# opticalDecoder.net
KiCad netlist of a schematic drawn in Altium Designer
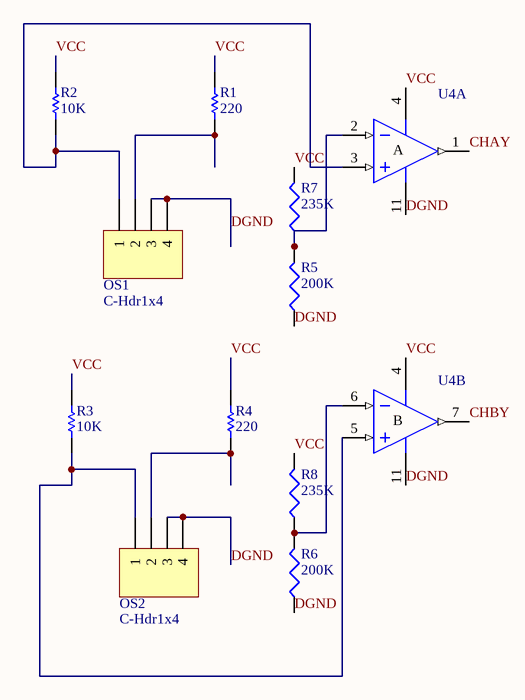
[diagram p0: opticalDecoder.SchDoc]

(export (version "E")
  (design (tool "Eeschema 10.0.6"))
  (components
    (comp (ref "OS1")
      (value "C-Hdr1x4")
      (footprint "HDR1X4_LGE1.0")
      (description "Header, 4-Pin")
      (fields (field (name "PUBLISHER") "Altium Limited"))
      (libsource (lib "PartsDatabaseV13p1") (part "C-Hdr1x4"))
    )
    (comp (ref "OS2")
      (value "C-Hdr1x4")
      (footprint "HDR1X4_LGE1.0")
      (description "Header, 4-Pin")
      (fields (field (name "PUBLISHER") "Altium Limited"))
      (libsource (lib "PartsDatabaseV13p1") (part "C-Hdr1x4"))
    )
    (comp (ref "R1")
      (value "220")
      (footprint "Res10mm_LGE1.0")
      (description "Resistor")
      (fields (field (name "PUBLISHER") "Altium Limited"))
      (libsource (lib "Miscellaneous Devices") (part "Res1"))
    )
    (comp (ref "R2")
      (value "10K")
      (footprint "Res10mm_LGE1.0")
      (description "Resistor")
      (fields (field (name "PUBLISHER") "Altium Limited"))
      (libsource (lib "Miscellaneous Devices") (part "Res1"))
    )
    (comp (ref "R3")
      (value "10K")
      (footprint "Res10mm_LGE1.0")
      (description "Resistor")
      (fields (field (name "PUBLISHER") "Altium Limited"))
      (libsource (lib "Miscellaneous Devices") (part "Res1"))
    )
    (comp (ref "R4")
      (value "220")
      (footprint "Res10mm_LGE1.0")
      (description "Resistor")
      (fields (field (name "PUBLISHER") "Altium Limited"))
      (libsource (lib "Miscellaneous Devices") (part "Res1"))
    )
    (comp (ref "R5")
      (value "200K")
      (footprint "Res10mm_LGE1.0")
      (description "resistor (specify value)")
      (fields (field (name "PUBLISHER") "Altium Limited"))
      (libsource (lib "PartsDatabaseV13p1") (part "G-Res"))
    )
    (comp (ref "R6")
      (value "200K")
      (footprint "Res10mm_LGE1.0")
      (description "resistor (specify value)")
      (fields (field (name "PUBLISHER") "Altium Limited"))
      (libsource (lib "PartsDatabaseV13p1") (part "G-Res"))
    )
    (comp (ref "R7")
      (value "235K")
      (footprint "Res10mm_LGE1.0")
      (description "resistor (specify value)")
      (fields (field (name "PUBLISHER") "Altium Limited"))
      (libsource (lib "PartsDatabaseV13p1") (part "G-Res"))
    )
    (comp (ref "R8")
      (value "235K")
      (footprint "Res10mm_LGE1.0")
      (description "resistor (specify value)")
      (fields (field (name "PUBLISHER") "Altium Limited"))
      (libsource (lib "PartsDatabaseV13p1") (part "G-Res"))
    )
    (comp (ref "U4")
      (value "O-OpAmp074")
      (footprint "DIP14_LGE1.0")
      (description "op amp (TL074)")
      (fields (field (name "PUBLISHER") "Altium Limited"))
      (libsource (lib "PartsDatabaseV13p1") (part "O-OpAmp074"))
    )
  )
  (nets
    (net (code "1") (name "/CHAY") (class "Default")
      (node (ref "U4") (pin "1") (pinfunction "OUT_1") (pintype "output"))
    )
    (net (code "2") (name "/CHBY") (class "Default")
      (node (ref "U4") (pin "7") (pinfunction "OUT_7") (pintype "output"))
    )
    (net (code "3") (name "/DGND") (class "Default")
      (node (ref "OS1") (pin "3") (pinfunction "3_3") (pintype "passive"))
      (node (ref "OS1") (pin "4") (pinfunction "4_4") (pintype "passive"))
      (node (ref "OS2") (pin "3") (pinfunction "3_3") (pintype "passive"))
      (node (ref "OS2") (pin "4") (pinfunction "4_4") (pintype "passive"))
      (node (ref "R5") (pin "1") (pinfunction "1_1") (pintype "passive"))
      (node (ref "R6") (pin "1") (pinfunction "1_1") (pintype "passive"))
      (node (ref "U4") (pin "11") (pinfunction "V-_11") (pintype "power_in"))
    )
    (net (code "4") (name "/VCC") (class "Default")
      (node (ref "R1") (pin "2") (pinfunction "2_2") (pintype "passive"))
      (node (ref "R2") (pin "2") (pinfunction "2_2") (pintype "passive"))
      (node (ref "R3") (pin "2") (pinfunction "2_2") (pintype "passive"))
      (node (ref "R4") (pin "2") (pinfunction "2_2") (pintype "passive"))
      (node (ref "R7") (pin "2") (pinfunction "2_2") (pintype "passive"))
      (node (ref "R8") (pin "2") (pinfunction "2_2") (pintype "passive"))
      (node (ref "U4") (pin "4") (pinfunction "V+_4") (pintype "power_in"))
    )
    (net (code "5") (name "Net-(OS1-Pad2)") (class "Default")
      (node (ref "OS1") (pin "2") (pinfunction "2_2") (pintype "passive"))
      (node (ref "R1") (pin "1") (pinfunction "1_1") (pintype "passive"))
    )
    (net (code "6") (name "Net-(OS2-Pad2)") (class "Default")
      (node (ref "OS2") (pin "2") (pinfunction "2_2") (pintype "passive"))
      (node (ref "R4") (pin "1") (pinfunction "1_1") (pintype "passive"))
    )
    (net (code "7") (name "Net-(U4A-IN+)") (class "Default")
      (node (ref "OS1") (pin "1") (pinfunction "1_1") (pintype "passive"))
      (node (ref "R2") (pin "1") (pinfunction "1_1") (pintype "passive"))
      (node (ref "U4") (pin "3") (pinfunction "IN+_3") (pintype "input"))
    )
    (net (code "8") (name "Net-(U4A-IN-)") (class "Default")
      (node (ref "R5") (pin "2") (pinfunction "2_2") (pintype "passive"))
      (node (ref "R7") (pin "1") (pinfunction "1_1") (pintype "passive"))
      (node (ref "U4") (pin "2") (pinfunction "IN-_2") (pintype "input"))
    )
    (net (code "9") (name "Net-(U4B-IN+)") (class "Default")
      (node (ref "OS2") (pin "1") (pinfunction "1_1") (pintype "passive"))
      (node (ref "R3") (pin "1") (pinfunction "1_1") (pintype "passive"))
      (node (ref "U4") (pin "5") (pinfunction "IN+_5") (pintype "input"))
    )
    (net (code "10") (name "Net-(U4B-IN-)") (class "Default")
      (node (ref "R6") (pin "2") (pinfunction "2_2") (pintype "passive"))
      (node (ref "R8") (pin "1") (pinfunction "1_1") (pintype "passive"))
      (node (ref "U4") (pin "6") (pinfunction "IN-_6") (pintype "input"))
    )
  )
)
